# Proto_RS485_ISO.net
KiCad netlist of a schematic drawn in EAGLE
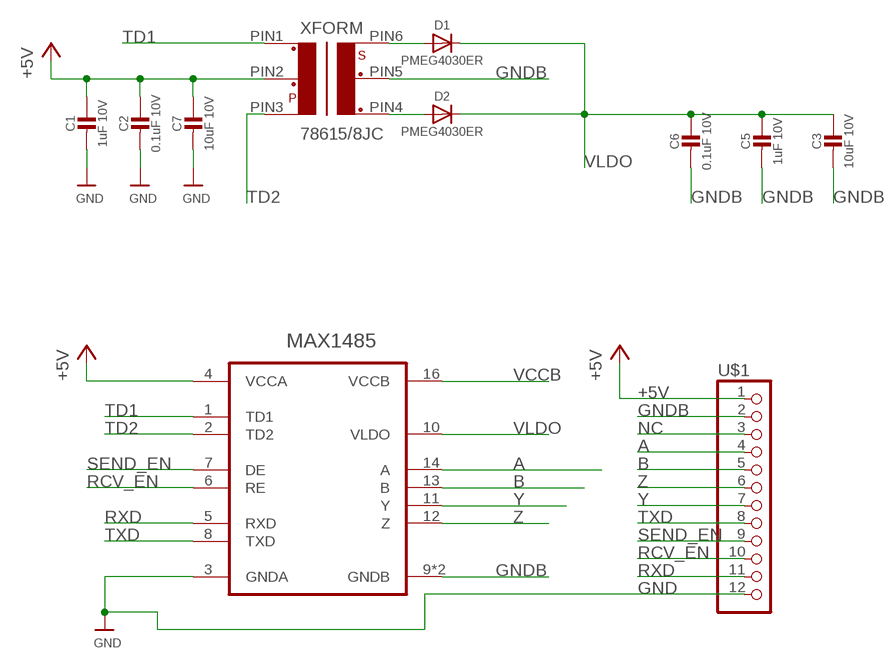
[diagram p0: schematic, sheet 1]

(export (version "E")
  (design (tool "Eeschema 10.0.6"))
  (components
    (comp (ref "C1")
      (value "1uF 10V")
      (footprint "eagle-import:0603-MINI")
      (libsource (lib "eagle-import") (part "CAP_CERAMIC0603MINI"))
    )
    (comp (ref "C2")
      (value "0.1uF 10V")
      (footprint "eagle-import:0603-MINI")
      (libsource (lib "eagle-import") (part "CAP_CERAMIC0603MINI"))
    )
    (comp (ref "C3")
      (value "10uF 10V")
      (footprint "eagle-import:0603-MINI")
      (libsource (lib "eagle-import") (part "CAP_CERAMIC0603MINI"))
    )
    (comp (ref "C5")
      (value "1uF 10V")
      (footprint "eagle-import:0603-MINI")
      (libsource (lib "eagle-import") (part "CAP_CERAMIC0603MINI"))
    )
    (comp (ref "C6")
      (value "0.1uF 10V")
      (footprint "eagle-import:0603-MINI")
      (libsource (lib "eagle-import") (part "CAP_CERAMIC0603MINI"))
    )
    (comp (ref "C7")
      (value "10uF 10V")
      (footprint "eagle-import:0603-MINI")
      (libsource (lib "eagle-import") (part "CAP_CERAMIC0603MINI"))
    )
    (comp (ref "D1")
      (value "PMEG4030ER")
      (footprint "eagle-import:SOD-123")
      (libsource (lib "eagle-import") (part "DIODESOD-123"))
    )
    (comp (ref "D2")
      (value "PMEG4030ER")
      (footprint "eagle-import:SOD-123")
      (libsource (lib "eagle-import") (part "DIODESOD-123"))
    )
    (comp (ref "MAX1485")
      (value "MAX14853GWE+")
      (footprint "eagle-import:SOIC127P1034X267-16N")
      (libsource (lib "eagle-import") (part "MAX14853GWE+"))
    )
    (comp (ref "U$1")
      (value "PINHD-1X12")
      (footprint "eagle-import:1X12")
      (libsource (lib "eagle-import") (part "PINHD-1X12"))
    )
    (comp (ref "XFORM")
      (value "78615/8JC")
      (footprint "eagle-import:0.1_SMD")
      (libsource (lib "eagle-import") (part "78615/8JC"))
    )
  )
  (nets
    (net (code "1") (name "+5V") (class "Default")
      (node (ref "C1") (pin "1") (pinfunction "1_1") (pintype "passive"))
      (node (ref "C2") (pin "1") (pinfunction "1_1") (pintype "passive"))
      (node (ref "C7") (pin "1") (pinfunction "1_1") (pintype "passive"))
      (node (ref "MAX1485") (pin "4") (pinfunction "VCCA_4") (pintype "power_in"))
      (node (ref "U$1") (pin "1") (pinfunction "1_1") (pintype "passive"))
      (node (ref "XFORM") (pin "PIN2") (pinfunction "2_PIN2") (pintype "passive"))
    )
    (net (code "2") (name "/A") (class "Default")
      (node (ref "MAX1485") (pin "14") (pinfunction "A_14") (pintype "bidirectional"))
      (node (ref "U$1") (pin "4") (pinfunction "4_4") (pintype "passive"))
    )
    (net (code "3") (name "/B") (class "Default")
      (node (ref "MAX1485") (pin "13") (pinfunction "B_13") (pintype "bidirectional"))
      (node (ref "U$1") (pin "5") (pinfunction "5_5") (pintype "passive"))
    )
    (net (code "4") (name "/GNDB") (class "Default")
      (node (ref "C3") (pin "2") (pinfunction "2_2") (pintype "passive"))
      (node (ref "C5") (pin "2") (pinfunction "2_2") (pintype "passive"))
      (node (ref "C6") (pin "2") (pinfunction "2_2") (pintype "passive"))
      (node (ref "MAX1485") (pin "15") (pinfunction "GNDB_15") (pintype "bidirectional"))
      (node (ref "MAX1485") (pin "9") (pinfunction "GNDB_9") (pintype "bidirectional"))
      (node (ref "U$1") (pin "2") (pinfunction "2_2") (pintype "passive"))
      (node (ref "XFORM") (pin "PIN5") (pinfunction "5_PIN5") (pintype "passive"))
    )
    (net (code "5") (name "/NC") (class "Default")
      (node (ref "U$1") (pin "3") (pinfunction "3_3") (pintype "passive"))
    )
    (net (code "6") (name "/RCV_EN") (class "Default")
      (node (ref "MAX1485") (pin "6") (pinfunction "RE_6") (pintype "input"))
      (node (ref "U$1") (pin "10") (pinfunction "10_10") (pintype "passive"))
    )
    (net (code "7") (name "/RXD") (class "Default")
      (node (ref "MAX1485") (pin "5") (pinfunction "RXD_5") (pintype "input"))
      (node (ref "U$1") (pin "11") (pinfunction "11_11") (pintype "passive"))
    )
    (net (code "8") (name "/SEND_EN") (class "Default")
      (node (ref "MAX1485") (pin "7") (pinfunction "DE_7") (pintype "input"))
      (node (ref "U$1") (pin "9") (pinfunction "9_9") (pintype "passive"))
    )
    (net (code "9") (name "/TD1") (class "Default")
      (node (ref "MAX1485") (pin "1") (pinfunction "TD1_1") (pintype "bidirectional"))
      (node (ref "XFORM") (pin "PIN1") (pinfunction "1_PIN1") (pintype "passive"))
    )
    (net (code "10") (name "/TD2") (class "Default")
      (node (ref "MAX1485") (pin "2") (pinfunction "TD2_2") (pintype "bidirectional"))
      (node (ref "XFORM") (pin "PIN3") (pinfunction "3_PIN3") (pintype "passive"))
    )
    (net (code "11") (name "/TXD") (class "Default")
      (node (ref "MAX1485") (pin "8") (pinfunction "TXD_8") (pintype "input"))
      (node (ref "U$1") (pin "8") (pinfunction "8_8") (pintype "passive"))
    )
    (net (code "12") (name "/VCCB") (class "Default")
      (node (ref "MAX1485") (pin "16") (pinfunction "VCCB_16") (pintype "bidirectional"))
    )
    (net (code "13") (name "/VLDO") (class "Default")
      (node (ref "C3") (pin "1") (pinfunction "1_1") (pintype "passive"))
      (node (ref "C5") (pin "1") (pinfunction "1_1") (pintype "passive"))
      (node (ref "C6") (pin "1") (pinfunction "1_1") (pintype "passive"))
      (node (ref "D1") (pin "C") (pinfunction "C_C") (pintype "passive"))
      (node (ref "D2") (pin "C") (pinfunction "C_C") (pintype "passive"))
      (node (ref "MAX1485") (pin "10") (pinfunction "VLDO_10") (pintype "output"))
    )
    (net (code "14") (name "/Y") (class "Default")
      (node (ref "MAX1485") (pin "11") (pinfunction "Y_11") (pintype "bidirectional"))
      (node (ref "U$1") (pin "7") (pinfunction "7_7") (pintype "passive"))
    )
    (net (code "15") (name "/Z") (class "Default")
      (node (ref "MAX1485") (pin "12") (pinfunction "Z_12") (pintype "bidirectional"))
      (node (ref "U$1") (pin "6") (pinfunction "6_6") (pintype "passive"))
    )
    (net (code "16") (name "GND") (class "Default")
      (node (ref "C1") (pin "2") (pinfunction "2_2") (pintype "passive"))
      (node (ref "C2") (pin "2") (pinfunction "2_2") (pintype "passive"))
      (node (ref "C7") (pin "2") (pinfunction "2_2") (pintype "passive"))
      (node (ref "MAX1485") (pin "3") (pinfunction "GNDA_3") (pintype "passive"))
      (node (ref "U$1") (pin "12") (pinfunction "12_12") (pintype "passive"))
    )
    (net (code "17") (name "Net-(XFORM-4)") (class "Default")
      (node (ref "D2") (pin "A") (pinfunction "A_A") (pintype "passive"))
      (node (ref "XFORM") (pin "PIN4") (pinfunction "4_PIN4") (pintype "passive"))
    )
    (net (code "18") (name "Net-(XFORM-6)") (class "Default")
      (node (ref "D1") (pin "A") (pinfunction "A_A") (pintype "passive"))
      (node (ref "XFORM") (pin "PIN6") (pinfunction "6_PIN6") (pintype "passive"))
    )
  )
)
